# XC6SLX09-2FTG256C.net
KiCad netlist of a schematic drawn in Altium Designer
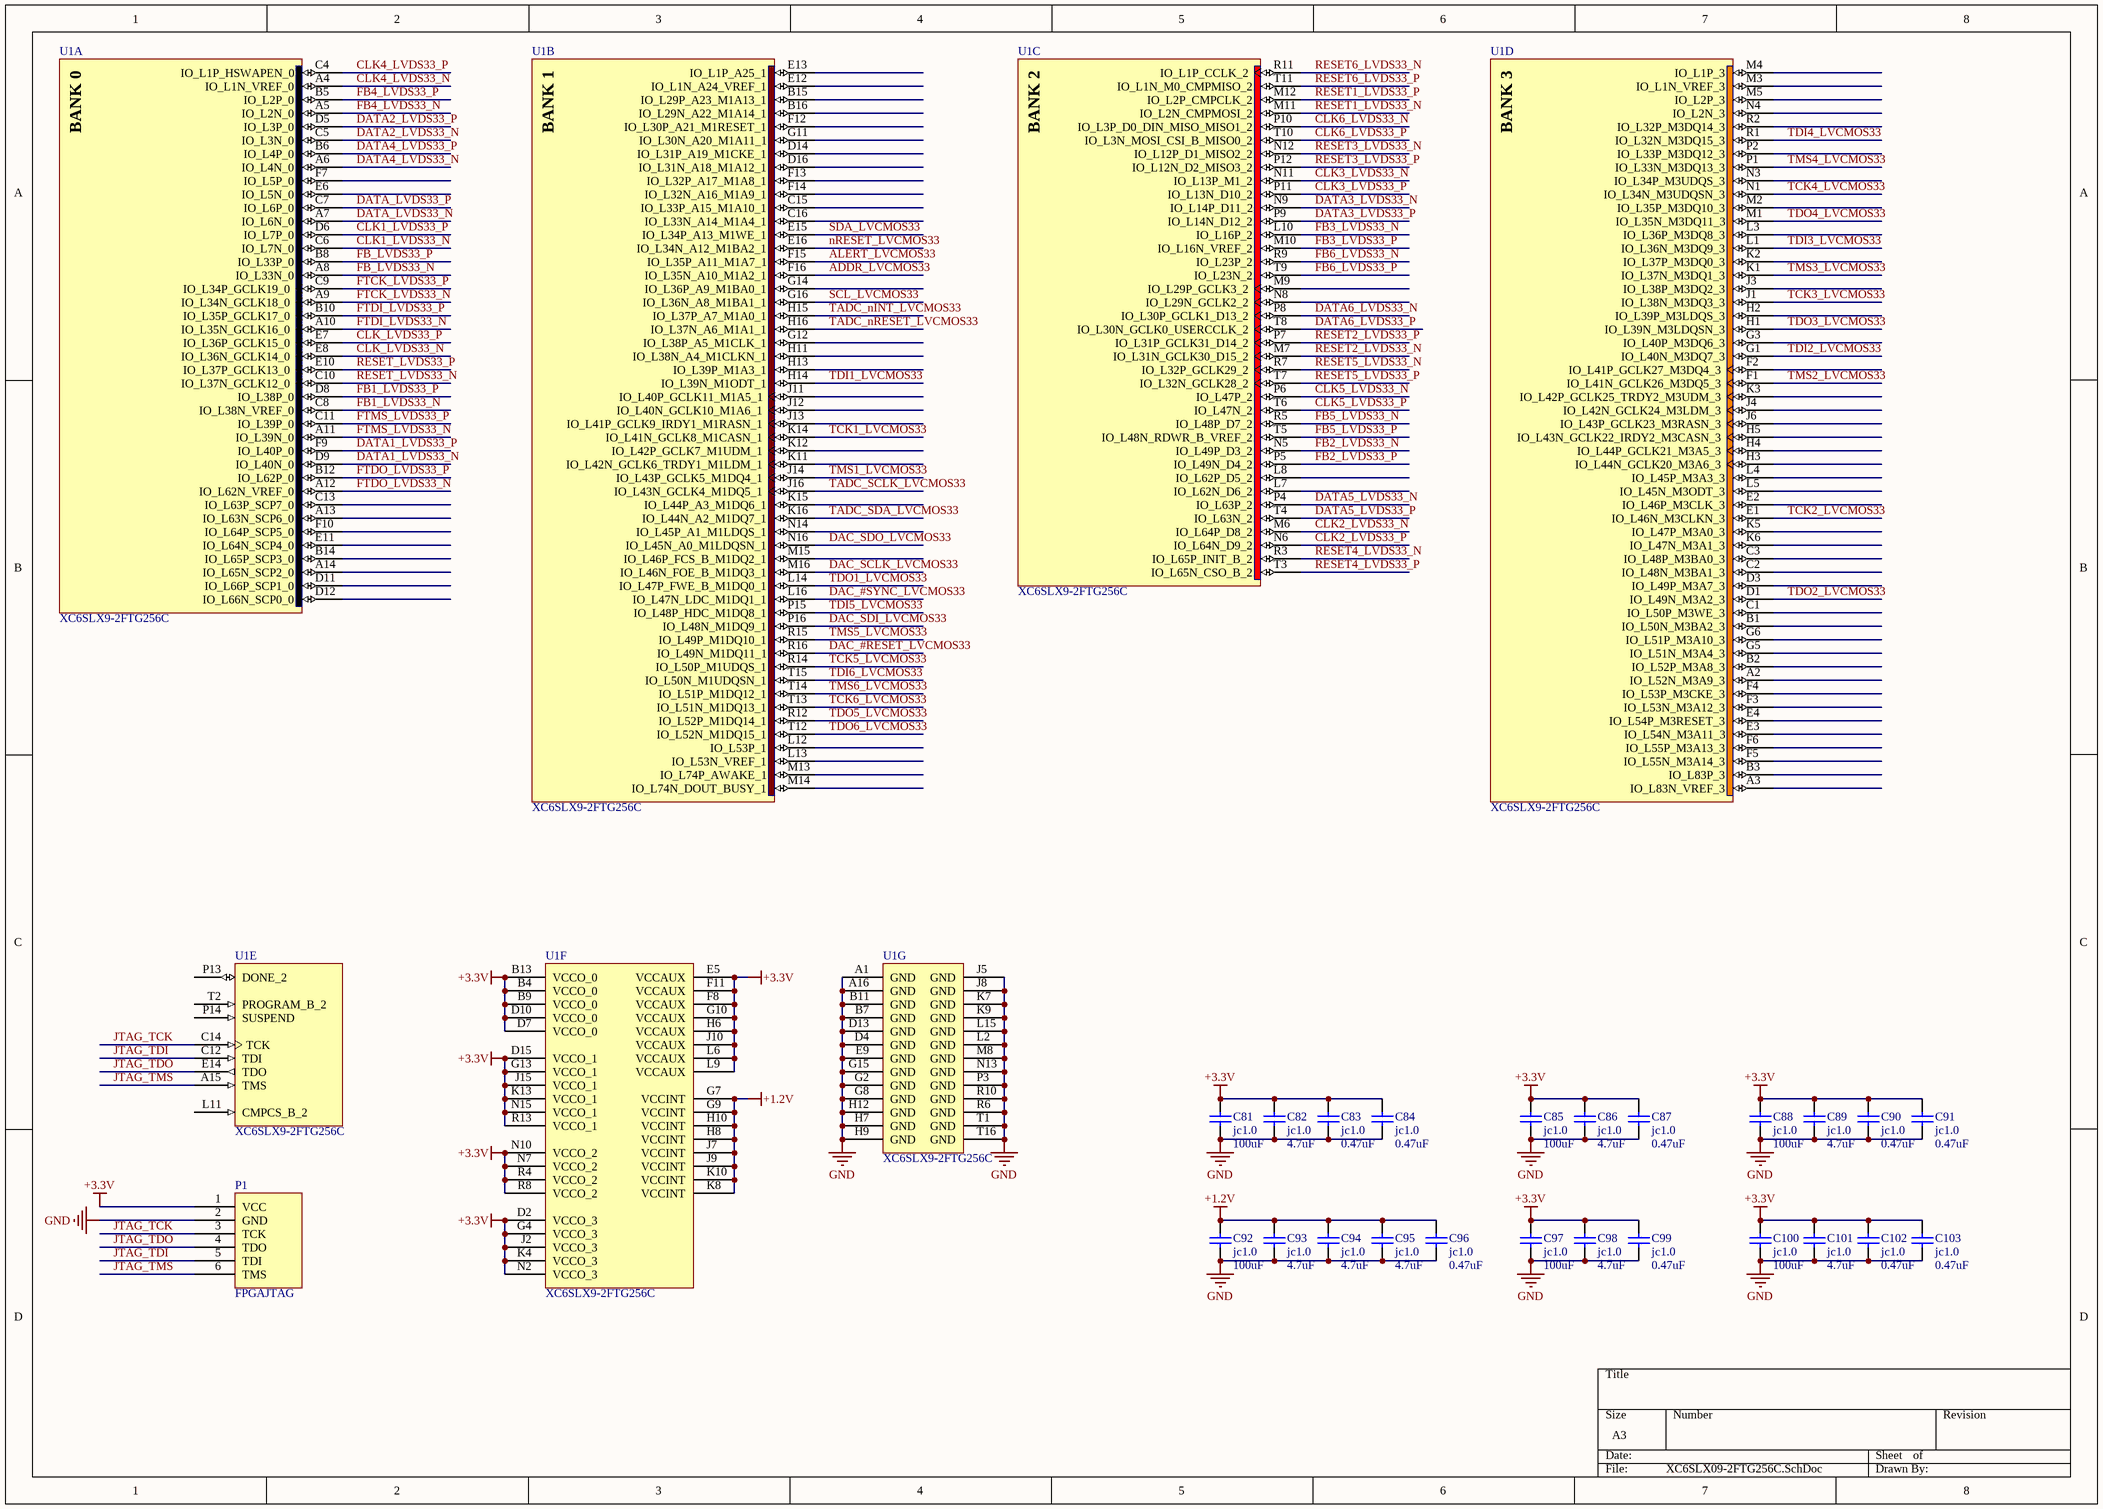
[diagram p0: XC6SLX09-2FTG256C.SchDoc]

(export (version "E")
  (design (tool "Eeschema 10.0.6"))
  (components
    (comp (ref "C81")
      (value "jc1.0")
      (footprint "0805")
      (description "Capacitor")
      (fields (field (name "ALTIUM_VALUE") "100uF") (field (name "PUBLISHER") "Altium Limited"))
      (libsource (lib "LIB01DXP2006SchLib") (part "Cap"))
    )
    (comp (ref "C82")
      (value "jc1.0")
      (footprint "0402")
      (description "Capacitor")
      (fields (field (name "ALTIUM_VALUE") "4.7uF") (field (name "PUBLISHER") "Altium Limited"))
      (libsource (lib "LIB01DXP2006SchLib") (part "Cap"))
    )
    (comp (ref "C83")
      (value "jc1.0")
      (footprint "0402")
      (description "Capacitor")
      (fields (field (name "ALTIUM_VALUE") "0.47uF") (field (name "PUBLISHER") "Altium Limited"))
      (libsource (lib "LIB01DXP2006SchLib") (part "Cap"))
    )
    (comp (ref "C84")
      (value "jc1.0")
      (footprint "0402")
      (description "Capacitor")
      (fields (field (name "ALTIUM_VALUE") "0.47uF") (field (name "PUBLISHER") "Altium Limited"))
      (libsource (lib "LIB01DXP2006SchLib") (part "Cap"))
    )
    (comp (ref "C85")
      (value "jc1.0")
      (footprint "0805")
      (description "Capacitor")
      (fields (field (name "ALTIUM_VALUE") "100uF") (field (name "PUBLISHER") "Altium Limited"))
      (libsource (lib "LIB01DXP2006SchLib") (part "Cap"))
    )
    (comp (ref "C86")
      (value "jc1.0")
      (footprint "0402")
      (description "Capacitor")
      (fields (field (name "ALTIUM_VALUE") "4.7uF") (field (name "PUBLISHER") "Altium Limited"))
      (libsource (lib "LIB01DXP2006SchLib") (part "Cap"))
    )
    (comp (ref "C87")
      (value "jc1.0")
      (footprint "0402")
      (description "Capacitor")
      (fields (field (name "ALTIUM_VALUE") "0.47uF") (field (name "PUBLISHER") "Altium Limited"))
      (libsource (lib "LIB01DXP2006SchLib") (part "Cap"))
    )
    (comp (ref "C88")
      (value "jc1.0")
      (footprint "0805")
      (description "Capacitor")
      (fields (field (name "ALTIUM_VALUE") "100uF") (field (name "PUBLISHER") "Altium Limited"))
      (libsource (lib "LIB01DXP2006SchLib") (part "Cap"))
    )
    (comp (ref "C89")
      (value "jc1.0")
      (footprint "0402")
      (description "Capacitor")
      (fields (field (name "ALTIUM_VALUE") "4.7uF") (field (name "PUBLISHER") "Altium Limited"))
      (libsource (lib "LIB01DXP2006SchLib") (part "Cap"))
    )
    (comp (ref "C90")
      (value "jc1.0")
      (footprint "0402")
      (description "Capacitor")
      (fields (field (name "ALTIUM_VALUE") "0.47uF") (field (name "PUBLISHER") "Altium Limited"))
      (libsource (lib "LIB01DXP2006SchLib") (part "Cap"))
    )
    (comp (ref "C91")
      (value "jc1.0")
      (footprint "0402")
      (description "Capacitor")
      (fields (field (name "ALTIUM_VALUE") "0.47uF") (field (name "PUBLISHER") "Altium Limited"))
      (libsource (lib "LIB01DXP2006SchLib") (part "Cap"))
    )
    (comp (ref "C92")
      (value "jc1.0")
      (footprint "0805")
      (description "Capacitor")
      (fields (field (name "ALTIUM_VALUE") "100uF") (field (name "PUBLISHER") "Altium Limited"))
      (libsource (lib "LIB01DXP2006SchLib") (part "Cap"))
    )
    (comp (ref "C93")
      (value "jc1.0")
      (footprint "0402")
      (description "Capacitor")
      (fields (field (name "ALTIUM_VALUE") "4.7uF") (field (name "PUBLISHER") "Altium Limited"))
      (libsource (lib "LIB01DXP2006SchLib") (part "Cap"))
    )
    (comp (ref "C94")
      (value "jc1.0")
      (footprint "0402")
      (description "Capacitor")
      (fields (field (name "ALTIUM_VALUE") "4.7uF") (field (name "PUBLISHER") "Altium Limited"))
      (libsource (lib "LIB01DXP2006SchLib") (part "Cap"))
    )
    (comp (ref "C95")
      (value "jc1.0")
      (footprint "0402")
      (description "Capacitor")
      (fields (field (name "ALTIUM_VALUE") "4.7uF") (field (name "PUBLISHER") "Altium Limited"))
      (libsource (lib "LIB01DXP2006SchLib") (part "Cap"))
    )
    (comp (ref "C96")
      (value "jc1.0")
      (footprint "0402")
      (description "Capacitor")
      (fields (field (name "ALTIUM_VALUE") "0.47uF") (field (name "PUBLISHER") "Altium Limited"))
      (libsource (lib "LIB01DXP2006SchLib") (part "Cap"))
    )
    (comp (ref "C97")
      (value "jc1.0")
      (footprint "0805")
      (description "Capacitor")
      (fields (field (name "ALTIUM_VALUE") "100uF") (field (name "PUBLISHER") "Altium Limited"))
      (libsource (lib "LIB01DXP2006SchLib") (part "Cap"))
    )
    (comp (ref "C98")
      (value "jc1.0")
      (footprint "0402")
      (description "Capacitor")
      (fields (field (name "ALTIUM_VALUE") "4.7uF") (field (name "PUBLISHER") "Altium Limited"))
      (libsource (lib "LIB01DXP2006SchLib") (part "Cap"))
    )
    (comp (ref "C99")
      (value "jc1.0")
      (footprint "0402")
      (description "Capacitor")
      (fields (field (name "ALTIUM_VALUE") "0.47uF") (field (name "PUBLISHER") "Altium Limited"))
      (libsource (lib "LIB01DXP2006SchLib") (part "Cap"))
    )
    (comp (ref "C100")
      (value "jc1.0")
      (footprint "0805")
      (description "Capacitor")
      (fields (field (name "ALTIUM_VALUE") "100uF") (field (name "PUBLISHER") "Altium Limited"))
      (libsource (lib "LIB01DXP2006SchLib") (part "Cap"))
    )
    (comp (ref "C101")
      (value "jc1.0")
      (footprint "0402")
      (description "Capacitor")
      (fields (field (name "ALTIUM_VALUE") "4.7uF") (field (name "PUBLISHER") "Altium Limited"))
      (libsource (lib "LIB01DXP2006SchLib") (part "Cap"))
    )
    (comp (ref "C102")
      (value "jc1.0")
      (footprint "0402")
      (description "Capacitor")
      (fields (field (name "ALTIUM_VALUE") "0.47uF") (field (name "PUBLISHER") "Altium Limited"))
      (libsource (lib "LIB01DXP2006SchLib") (part "Cap"))
    )
    (comp (ref "C103")
      (value "jc1.0")
      (footprint "0402")
      (description "Capacitor")
      (fields (field (name "ALTIUM_VALUE") "0.47uF") (field (name "PUBLISHER") "Altium Limited"))
      (libsource (lib "LIB01DXP2006SchLib") (part "Cap"))
    )
    (comp (ref "P1")
      (value "FPGAJTAG")
      (footprint "SIP6")
      (libsource (lib "LIB01DXP2006SchLib") (part "FPGAJTAGHEADER"))
    )
    (comp (ref "U1")
      (value "XC6SLX9-2FTG256C")
      (footprint "FTG256")
      (libsource (lib "Spartan-6") (part "XC6SLX9-2FTG256C"))
    )
  )
  (nets
    (net (code "1") (name "+1.2V") (class "Default")
      (node (ref "C92") (pin "2") (pinfunction "2_2") (pintype "passive"))
      (node (ref "C93") (pin "2") (pinfunction "2_2") (pintype "passive"))
      (node (ref "C94") (pin "2") (pinfunction "2_2") (pintype "passive"))
      (node (ref "C95") (pin "2") (pinfunction "2_2") (pintype "passive"))
      (node (ref "C96") (pin "2") (pinfunction "2_2") (pintype "passive"))
      (node (ref "U1") (pin "G7") (pinfunction "VCCINT_G7") (pintype "power_in"))
      (node (ref "U1") (pin "G9") (pinfunction "VCCINT_G9") (pintype "power_in"))
      (node (ref "U1") (pin "H10") (pinfunction "VCCINT_H10") (pintype "power_in"))
      (node (ref "U1") (pin "H8") (pinfunction "VCCINT_H8") (pintype "power_in"))
      (node (ref "U1") (pin "J7") (pinfunction "VCCINT_J7") (pintype "power_in"))
      (node (ref "U1") (pin "J9") (pinfunction "VCCINT_J9") (pintype "power_in"))
      (node (ref "U1") (pin "K10") (pinfunction "VCCINT_K10") (pintype "power_in"))
      (node (ref "U1") (pin "K8") (pinfunction "VCCINT_K8") (pintype "power_in"))
    )
    (net (code "2") (name "+3.3V") (class "Default")
      (node (ref "C100") (pin "2") (pinfunction "2_2") (pintype "passive"))
      (node (ref "C101") (pin "2") (pinfunction "2_2") (pintype "passive"))
      (node (ref "C102") (pin "2") (pinfunction "2_2") (pintype "passive"))
      (node (ref "C103") (pin "2") (pinfunction "2_2") (pintype "passive"))
      (node (ref "C81") (pin "2") (pinfunction "2_2") (pintype "passive"))
      (node (ref "C82") (pin "2") (pinfunction "2_2") (pintype "passive"))
      (node (ref "C83") (pin "2") (pinfunction "2_2") (pintype "passive"))
      (node (ref "C84") (pin "2") (pinfunction "2_2") (pintype "passive"))
      (node (ref "C85") (pin "2") (pinfunction "2_2") (pintype "passive"))
      (node (ref "C86") (pin "2") (pinfunction "2_2") (pintype "passive"))
      (node (ref "C87") (pin "2") (pinfunction "2_2") (pintype "passive"))
      (node (ref "C88") (pin "2") (pinfunction "2_2") (pintype "passive"))
      (node (ref "C89") (pin "2") (pinfunction "2_2") (pintype "passive"))
      (node (ref "C90") (pin "2") (pinfunction "2_2") (pintype "passive"))
      (node (ref "C91") (pin "2") (pinfunction "2_2") (pintype "passive"))
      (node (ref "C97") (pin "2") (pinfunction "2_2") (pintype "passive"))
      (node (ref "C98") (pin "2") (pinfunction "2_2") (pintype "passive"))
      (node (ref "C99") (pin "2") (pinfunction "2_2") (pintype "passive"))
      (node (ref "P1") (pin "1") (pinfunction "VCC_1") (pintype "passive"))
      (node (ref "U1") (pin "B13") (pinfunction "VCCO_0_B13") (pintype "power_in"))
      (node (ref "U1") (pin "B4") (pinfunction "VCCO_0_B4") (pintype "power_in"))
      (node (ref "U1") (pin "B9") (pinfunction "VCCO_0_B9") (pintype "power_in"))
      (node (ref "U1") (pin "D10") (pinfunction "VCCO_0_D10") (pintype "power_in"))
      (node (ref "U1") (pin "D15") (pinfunction "VCCO_1_D15") (pintype "power_in"))
      (node (ref "U1") (pin "D2") (pinfunction "VCCO_3_D2") (pintype "power_in"))
      (node (ref "U1") (pin "D7") (pinfunction "VCCO_0_D7") (pintype "power_in"))
      (node (ref "U1") (pin "E5") (pinfunction "VCCAUX_E5") (pintype "power_in"))
      (node (ref "U1") (pin "F11") (pinfunction "VCCAUX_F11") (pintype "power_in"))
      (node (ref "U1") (pin "F8") (pinfunction "VCCAUX_F8") (pintype "power_in"))
      (node (ref "U1") (pin "G10") (pinfunction "VCCAUX_G10") (pintype "power_in"))
      (node (ref "U1") (pin "G13") (pinfunction "VCCO_1_G13") (pintype "power_in"))
      (node (ref "U1") (pin "G4") (pinfunction "VCCO_3_G4") (pintype "power_in"))
      (node (ref "U1") (pin "H6") (pinfunction "VCCAUX_H6") (pintype "power_in"))
      (node (ref "U1") (pin "J10") (pinfunction "VCCAUX_J10") (pintype "power_in"))
      (node (ref "U1") (pin "J15") (pinfunction "VCCO_1_J15") (pintype "power_in"))
      (node (ref "U1") (pin "J2") (pinfunction "VCCO_3_J2") (pintype "power_in"))
      (node (ref "U1") (pin "K13") (pinfunction "VCCO_1_K13") (pintype "power_in"))
      (node (ref "U1") (pin "K4") (pinfunction "VCCO_3_K4") (pintype "power_in"))
      (node (ref "U1") (pin "L6") (pinfunction "VCCAUX_L6") (pintype "power_in"))
      (node (ref "U1") (pin "L9") (pinfunction "VCCAUX_L9") (pintype "power_in"))
      (node (ref "U1") (pin "N10") (pinfunction "VCCO_2_N10") (pintype "power_in"))
      (node (ref "U1") (pin "N15") (pinfunction "VCCO_1_N15") (pintype "power_in"))
      (node (ref "U1") (pin "N2") (pinfunction "VCCO_3_N2") (pintype "power_in"))
      (node (ref "U1") (pin "N7") (pinfunction "VCCO_2_N7") (pintype "power_in"))
      (node (ref "U1") (pin "R13") (pinfunction "VCCO_1_R13") (pintype "power_in"))
      (node (ref "U1") (pin "R4") (pinfunction "VCCO_2_R4") (pintype "power_in"))
      (node (ref "U1") (pin "R8") (pinfunction "VCCO_2_R8") (pintype "power_in"))
    )
    (net (code "3") (name "/ADDR_LVCMOS33") (class "Default")
      (node (ref "U1") (pin "F16") (pinfunction "IO_L35N_A10_M1A2_1_F16") (pintype "bidirectional"))
    )
    (net (code "4") (name "/ALERT_LVCMOS33") (class "Default")
      (node (ref "U1") (pin "F15") (pinfunction "IO_L35P_A11_M1A7_1_F15") (pintype "bidirectional"))
    )
    (net (code "5") (name "/CLK1_LVDS33_N") (class "Default")
      (node (ref "U1") (pin "C6") (pinfunction "IO_L7N_0_C6") (pintype "bidirectional"))
    )
    (net (code "6") (name "/CLK1_LVDS33_P") (class "Default")
      (node (ref "U1") (pin "D6") (pinfunction "IO_L7P_0_D6") (pintype "bidirectional"))
    )
    (net (code "7") (name "/CLK2_LVDS33_N") (class "Default")
      (node (ref "U1") (pin "M6") (pinfunction "IO_L64P_D8_2_M6") (pintype "bidirectional"))
    )
    (net (code "8") (name "/CLK2_LVDS33_P") (class "Default")
      (node (ref "U1") (pin "N6") (pinfunction "IO_L64N_D9_2_N6") (pintype "bidirectional"))
    )
    (net (code "9") (name "/CLK3_LVDS33_N") (class "Default")
      (node (ref "U1") (pin "N11") (pinfunction "IO_L13P_M1_2_N11") (pintype "bidirectional"))
    )
    (net (code "10") (name "/CLK3_LVDS33_P") (class "Default")
      (node (ref "U1") (pin "P11") (pinfunction "IO_L13N_D10_2_P11") (pintype "bidirectional"))
    )
    (net (code "11") (name "/CLK4_LVDS33_N") (class "Default")
      (node (ref "U1") (pin "A4") (pinfunction "IO_L1N_VREF_0_A4") (pintype "bidirectional"))
    )
    (net (code "12") (name "/CLK4_LVDS33_P") (class "Default")
      (node (ref "U1") (pin "C4") (pinfunction "IO_L1P_HSWAPEN_0_C4") (pintype "bidirectional"))
    )
    (net (code "13") (name "/CLK5_LVDS33_N") (class "Default")
      (node (ref "U1") (pin "P6") (pinfunction "IO_L47P_2_P6") (pintype "bidirectional"))
    )
    (net (code "14") (name "/CLK5_LVDS33_P") (class "Default")
      (node (ref "U1") (pin "T6") (pinfunction "IO_L47N_2_T6") (pintype "bidirectional"))
    )
    (net (code "15") (name "/CLK6_LVDS33_N") (class "Default")
      (node (ref "U1") (pin "P10") (pinfunction "IO_L3P_D0_DIN_MISO_MISO1_2_P10") (pintype "bidirectional"))
    )
    (net (code "16") (name "/CLK6_LVDS33_P") (class "Default")
      (node (ref "U1") (pin "T10") (pinfunction "IO_L3N_MOSI_CSI_B_MISO0_2_T10") (pintype "bidirectional"))
    )
    (net (code "17") (name "/CLK_LVDS33_N") (class "Default")
      (node (ref "U1") (pin "E8") (pinfunction "IO_L36N_GCLK14_0_E8") (pintype "bidirectional"))
    )
    (net (code "18") (name "/CLK_LVDS33_P") (class "Default")
      (node (ref "U1") (pin "E7") (pinfunction "IO_L36P_GCLK15_0_E7") (pintype "bidirectional"))
    )
    (net (code "19") (name "/DAC_#RESET_LVCMOS33") (class "Default")
      (node (ref "U1") (pin "R16") (pinfunction "IO_L49N_M1DQ11_1_R16") (pintype "bidirectional"))
    )
    (net (code "20") (name "/DAC_#SYNC_LVCMOS33") (class "Default")
      (node (ref "U1") (pin "L16") (pinfunction "IO_L47N_LDC_M1DQ1_1_L16") (pintype "bidirectional"))
    )
    (net (code "21") (name "/DAC_SCLK_LVCMOS33") (class "Default")
      (node (ref "U1") (pin "M16") (pinfunction "IO_L46N_FOE_B_M1DQ3_1_M16") (pintype "bidirectional"))
    )
    (net (code "22") (name "/DAC_SDI_LVCMOS33") (class "Default")
      (node (ref "U1") (pin "P16") (pinfunction "IO_L48N_M1DQ9_1_P16") (pintype "bidirectional"))
    )
    (net (code "23") (name "/DAC_SDO_LVCMOS33") (class "Default")
      (node (ref "U1") (pin "N16") (pinfunction "IO_L45N_A0_M1LDQSN_1_N16") (pintype "bidirectional"))
    )
    (net (code "24") (name "/DATA1_LVDS33_N") (class "Default")
      (node (ref "U1") (pin "D9") (pinfunction "IO_L40N_0_D9") (pintype "bidirectional"))
    )
    (net (code "25") (name "/DATA1_LVDS33_P") (class "Default")
      (node (ref "U1") (pin "F9") (pinfunction "IO_L40P_0_F9") (pintype "bidirectional"))
    )
    (net (code "26") (name "/DATA2_LVDS33_N") (class "Default")
      (node (ref "U1") (pin "C5") (pinfunction "IO_L3N_0_C5") (pintype "bidirectional"))
    )
    (net (code "27") (name "/DATA2_LVDS33_P") (class "Default")
      (node (ref "U1") (pin "D5") (pinfunction "IO_L3P_0_D5") (pintype "bidirectional"))
    )
    (net (code "28") (name "/DATA3_LVDS33_N") (class "Default")
      (node (ref "U1") (pin "N9") (pinfunction "IO_L14P_D11_2_N9") (pintype "bidirectional"))
    )
    (net (code "29") (name "/DATA3_LVDS33_P") (class "Default")
      (node (ref "U1") (pin "P9") (pinfunction "IO_L14N_D12_2_P9") (pintype "bidirectional"))
    )
    (net (code "30") (name "/DATA4_LVDS33_N") (class "Default")
      (node (ref "U1") (pin "A6") (pinfunction "IO_L4N_0_A6") (pintype "bidirectional"))
    )
    (net (code "31") (name "/DATA4_LVDS33_P") (class "Default")
      (node (ref "U1") (pin "B6") (pinfunction "IO_L4P_0_B6") (pintype "bidirectional"))
    )
    (net (code "32") (name "/DATA5_LVDS33_N") (class "Default")
      (node (ref "U1") (pin "P4") (pinfunction "IO_L63P_2_P4") (pintype "bidirectional"))
    )
    (net (code "33") (name "/DATA5_LVDS33_P") (class "Default")
      (node (ref "U1") (pin "T4") (pinfunction "IO_L63N_2_T4") (pintype "bidirectional"))
    )
    (net (code "34") (name "/DATA6_LVDS33_N") (class "Default")
      (node (ref "U1") (pin "P8") (pinfunction "IO_L30P_GCLK1_D13_2_P8") (pintype "bidirectional"))
    )
    (net (code "35") (name "/DATA6_LVDS33_P") (class "Default")
      (node (ref "U1") (pin "T8") (pinfunction "IO_L30N_GCLK0_USERCCLK_2_T8") (pintype "bidirectional"))
    )
    (net (code "36") (name "/DATA_LVDS33_N") (class "Default")
      (node (ref "U1") (pin "A7") (pinfunction "IO_L6N_0_A7") (pintype "bidirectional"))
    )
    (net (code "37") (name "/DATA_LVDS33_P") (class "Default")
      (node (ref "U1") (pin "C7") (pinfunction "IO_L6P_0_C7") (pintype "bidirectional"))
    )
    (net (code "38") (name "/FB1_LVDS33_N") (class "Default")
      (node (ref "U1") (pin "C8") (pinfunction "IO_L38N_VREF_0_C8") (pintype "bidirectional"))
    )
    (net (code "39") (name "/FB1_LVDS33_P") (class "Default")
      (node (ref "U1") (pin "D8") (pinfunction "IO_L38P_0_D8") (pintype "bidirectional"))
    )
    (net (code "40") (name "/FB2_LVDS33_N") (class "Default")
      (node (ref "U1") (pin "N5") (pinfunction "IO_L49P_D3_2_N5") (pintype "bidirectional"))
    )
    (net (code "41") (name "/FB2_LVDS33_P") (class "Default")
      (node (ref "U1") (pin "P5") (pinfunction "IO_L49N_D4_2_P5") (pintype "bidirectional"))
    )
    (net (code "42") (name "/FB3_LVDS33_N") (class "Default")
      (node (ref "U1") (pin "L10") (pinfunction "IO_L16P_2_L10") (pintype "bidirectional"))
    )
    (net (code "43") (name "/FB3_LVDS33_P") (class "Default")
      (node (ref "U1") (pin "M10") (pinfunction "IO_L16N_VREF_2_M10") (pintype "bidirectional"))
    )
    (net (code "44") (name "/FB4_LVDS33_N") (class "Default")
      (node (ref "U1") (pin "A5") (pinfunction "IO_L2N_0_A5") (pintype "bidirectional"))
    )
    (net (code "45") (name "/FB4_LVDS33_P") (class "Default")
      (node (ref "U1") (pin "B5") (pinfunction "IO_L2P_0_B5") (pintype "bidirectional"))
    )
    (net (code "46") (name "/FB5_LVDS33_N") (class "Default")
      (node (ref "U1") (pin "R5") (pinfunction "IO_L48P_D7_2_R5") (pintype "bidirectional"))
    )
    (net (code "47") (name "/FB5_LVDS33_P") (class "Default")
      (node (ref "U1") (pin "T5") (pinfunction "IO_L48N_RDWR_B_VREF_2_T5") (pintype "bidirectional"))
    )
    (net (code "48") (name "/FB6_LVDS33_N") (class "Default")
      (node (ref "U1") (pin "R9") (pinfunction "IO_L23P_2_R9") (pintype "bidirectional"))
    )
    (net (code "49") (name "/FB6_LVDS33_P") (class "Default")
      (node (ref "U1") (pin "T9") (pinfunction "IO_L23N_2_T9") (pintype "bidirectional"))
    )
    (net (code "50") (name "/FB_LVDS33_N") (class "Default")
      (node (ref "U1") (pin "A8") (pinfunction "IO_L33N_0_A8") (pintype "bidirectional"))
    )
    (net (code "51") (name "/FB_LVDS33_P") (class "Default")
      (node (ref "U1") (pin "B8") (pinfunction "IO_L33P_0_B8") (pintype "bidirectional"))
    )
    (net (code "52") (name "/FTCK_LVDS33_N") (class "Default")
      (node (ref "U1") (pin "A9") (pinfunction "IO_L34N_GCLK18_0_A9") (pintype "bidirectional"))
    )
    (net (code "53") (name "/FTCK_LVDS33_P") (class "Default")
      (node (ref "U1") (pin "C9") (pinfunction "IO_L34P_GCLK19_0_C9") (pintype "bidirectional"))
    )
    (net (code "54") (name "/FTDI_LVDS33_N") (class "Default")
      (node (ref "U1") (pin "A10") (pinfunction "IO_L35N_GCLK16_0_A10") (pintype "bidirectional"))
    )
    (net (code "55") (name "/FTDI_LVDS33_P") (class "Default")
      (node (ref "U1") (pin "B10") (pinfunction "IO_L35P_GCLK17_0_B10") (pintype "bidirectional"))
    )
    (net (code "56") (name "/FTDO_LVDS33_N") (class "Default")
      (node (ref "U1") (pin "A12") (pinfunction "IO_L62N_VREF_0_A12") (pintype "bidirectional"))
    )
    (net (code "57") (name "/FTDO_LVDS33_P") (class "Default")
      (node (ref "U1") (pin "B12") (pinfunction "IO_L62P_0_B12") (pintype "bidirectional"))
    )
    (net (code "58") (name "/FTMS_LVDS33_N") (class "Default")
      (node (ref "U1") (pin "A11") (pinfunction "IO_L39N_0_A11") (pintype "bidirectional"))
    )
    (net (code "59") (name "/FTMS_LVDS33_P") (class "Default")
      (node (ref "U1") (pin "C11") (pinfunction "IO_L39P_0_C11") (pintype "bidirectional"))
    )
    (net (code "60") (name "/JTAG_TCK") (class "Default")
      (node (ref "P1") (pin "3") (pinfunction "TCK_3") (pintype "passive"))
      (node (ref "U1") (pin "C14") (pinfunction "TCK_C14") (pintype "input"))
    )
    (net (code "61") (name "/JTAG_TDI") (class "Default")
      (node (ref "P1") (pin "5") (pinfunction "TDI_5") (pintype "passive"))
      (node (ref "U1") (pin "C12") (pinfunction "TDI_C12") (pintype "input"))
    )
    (net (code "62") (name "/JTAG_TDO") (class "Default")
      (node (ref "P1") (pin "4") (pinfunction "TDO_4") (pintype "passive"))
      (node (ref "U1") (pin "E14") (pinfunction "TDO_E14") (pintype "output"))
    )
    (net (code "63") (name "/JTAG_TMS") (class "Default")
      (node (ref "P1") (pin "6") (pinfunction "TMS_6") (pintype "passive"))
      (node (ref "U1") (pin "A15") (pinfunction "TMS_A15") (pintype "input"))
    )
    (net (code "64") (name "/RESET1_LVDS33_N") (class "Default")
      (node (ref "U1") (pin "M11") (pinfunction "IO_L2N_CMPMOSI_2_M11") (pintype "bidirectional"))
    )
    (net (code "65") (name "/RESET1_LVDS33_P") (class "Default")
      (node (ref "U1") (pin "M12") (pinfunction "IO_L2P_CMPCLK_2_M12") (pintype "bidirectional"))
    )
    (net (code "66") (name "/RESET2_LVDS33_N") (class "Default")
      (node (ref "U1") (pin "M7") (pinfunction "IO_L31N_GCLK30_D15_2_M7") (pintype "bidirectional"))
    )
    (net (code "67") (name "/RESET2_LVDS33_P") (class "Default")
      (node (ref "U1") (pin "P7") (pinfunction "IO_L31P_GCLK31_D14_2_P7") (pintype "bidirectional"))
    )
    (net (code "68") (name "/RESET3_LVDS33_N") (class "Default")
      (node (ref "U1") (pin "N12") (pinfunction "IO_L12P_D1_MISO2_2_N12") (pintype "bidirectional"))
    )
    (net (code "69") (name "/RESET3_LVDS33_P") (class "Default")
      (node (ref "U1") (pin "P12") (pinfunction "IO_L12N_D2_MISO3_2_P12") (pintype "bidirectional"))
    )
    (net (code "70") (name "/RESET4_LVDS33_N") (class "Default")
      (node (ref "U1") (pin "R3") (pinfunction "IO_L65P_INIT_B_2_R3") (pintype "bidirectional"))
    )
    (net (code "71") (name "/RESET4_LVDS33_P") (class "Default")
      (node (ref "U1") (pin "T3") (pinfunction "IO_L65N_CSO_B_2_T3") (pintype "bidirectional"))
    )
    (net (code "72") (name "/RESET5_LVDS33_N") (class "Default")
      (node (ref "U1") (pin "R7") (pinfunction "IO_L32P_GCLK29_2_R7") (pintype "bidirectional"))
    )
    (net (code "73") (name "/RESET5_LVDS33_P") (class "Default")
      (node (ref "U1") (pin "T7") (pinfunction "IO_L32N_GCLK28_2_T7") (pintype "bidirectional"))
    )
    (net (code "74") (name "/RESET6_LVDS33_N") (class "Default")
      (node (ref "U1") (pin "R11") (pinfunction "IO_L1P_CCLK_2_R11") (pintype "bidirectional"))
    )
    (net (code "75") (name "/RESET6_LVDS33_P") (class "Default")
      (node (ref "U1") (pin "T11") (pinfunction "IO_L1N_M0_CMPMISO_2_T11") (pintype "bidirectional"))
    )
    (net (code "76") (name "/RESET_LVDS33_N") (class "Default")
      (node (ref "U1") (pin "C10") (pinfunction "IO_L37N_GCLK12_0_C10") (pintype "bidirectional"))
    )
    (net (code "77") (name "/RESET_LVDS33_P") (class "Default")
      (node (ref "U1") (pin "E10") (pinfunction "IO_L37P_GCLK13_0_E10") (pintype "bidirectional"))
    )
    (net (code "78") (name "/SCL_LVCMOS33") (class "Default")
      (node (ref "U1") (pin "G16") (pinfunction "IO_L36N_A8_M1BA1_1_G16") (pintype "bidirectional"))
    )
    (net (code "79") (name "/SDA_LVCMOS33") (class "Default")
      (node (ref "U1") (pin "E15") (pinfunction "IO_L34P_A13_M1WE_1_E15") (pintype "bidirectional"))
    )
    (net (code "80") (name "/TADC_SCLK_LVCMOS33") (class "Default")
      (node (ref "U1") (pin "J16") (pinfunction "IO_L43N_GCLK4_M1DQ5_1_J16") (pintype "bidirectional"))
    )
    (net (code "81") (name "/TADC_SDA_LVCMOS33") (class "Default")
      (node (ref "U1") (pin "K16") (pinfunction "IO_L44N_A2_M1DQ7_1_K16") (pintype "bidirectional"))
    )
    (net (code "82") (name "/TADC_nINT_LVCMOS33") (class "Default")
      (node (ref "U1") (pin "H15") (pinfunction "IO_L37P_A7_M1A0_1_H15") (pintype "bidirectional"))
    )
    (net (code "83") (name "/TADC_nRESET_LVCMOS33") (class "Default")
      (node (ref "U1") (pin "H16") (pinfunction "IO_L37N_A6_M1A1_1_H16") (pintype "bidirectional"))
    )
    (net (code "84") (name "/TCK1_LVCMOS33") (class "Default")
      (node (ref "U1") (pin "K14") (pinfunction "IO_L41N_GCLK8_M1CASN_1_K14") (pintype "bidirectional"))
    )
    (net (code "85") (name "/TCK2_LVCMOS33") (class "Default")
      (node (ref "U1") (pin "E1") (pinfunction "IO_L46N_M3CLKN_3_E1") (pintype "bidirectional"))
    )
    (net (code "86") (name "/TCK3_LVCMOS33") (class "Default")
      (node (ref "U1") (pin "J1") (pinfunction "IO_L38N_M3DQ3_3_J1") (pintype "bidirectional"))
    )
    (net (code "87") (name "/TCK4_LVCMOS33") (class "Default")
      (node (ref "U1") (pin "N1") (pinfunction "IO_L34N_M3UDQSN_3_N1") (pintype "bidirectional"))
    )
    (net (code "88") (name "/TCK5_LVCMOS33") (class "Default")
      (node (ref "U1") (pin "R14") (pinfunction "IO_L50P_M1UDQS_1_R14") (pintype "bidirectional"))
    )
    (net (code "89") (name "/TCK6_LVCMOS33") (class "Default")
      (node (ref "U1") (pin "T13") (pinfunction "IO_L51N_M1DQ13_1_T13") (pintype "bidirectional"))
    )
    (net (code "90") (name "/TDI1_LVCMOS33") (class "Default")
      (node (ref "U1") (pin "H14") (pinfunction "IO_L39N_M1ODT_1_H14") (pintype "bidirectional"))
    )
    (net (code "91") (name "/TDI2_LVCMOS33") (class "Default")
      (node (ref "U1") (pin "G1") (pinfunction "IO_L40N_M3DQ7_3_G1") (pintype "bidirectional"))
    )
    (net (code "92") (name "/TDI3_LVCMOS33") (class "Default")
      (node (ref "U1") (pin "L1") (pinfunction "IO_L36N_M3DQ9_3_L1") (pintype "bidirectional"))
    )
    (net (code "93") (name "/TDI4_LVCMOS33") (class "Default")
      (node (ref "U1") (pin "R1") (pinfunction "IO_L32N_M3DQ15_3_R1") (pintype "bidirectional"))
    )
    (net (code "94") (name "/TDI5_LVCMOS33") (class "Default")
      (node (ref "U1") (pin "P15") (pinfunction "IO_L48P_HDC_M1DQ8_1_P15") (pintype "bidirectional"))
    )
    (net (code "95") (name "/TDI6_LVCMOS33") (class "Default")
      (node (ref "U1") (pin "T15") (pinfunction "IO_L50N_M1UDQSN_1_T15") (pintype "bidirectional"))
    )
    (net (code "96") (name "/TDO1_LVCMOS33") (class "Default")
      (node (ref "U1") (pin "L14") (pinfunction "IO_L47P_FWE_B_M1DQ0_1_L14") (pintype "bidirectional"))
    )
    (net (code "97") (name "/TDO2_LVCMOS33") (class "Default")
      (node (ref "U1") (pin "D1") (pinfunction "IO_L49N_M3A2_3_D1") (pintype "bidirectional"))
    )
    (net (code "98") (name "/TDO3_LVCMOS33") (class "Default")
      (node (ref "U1") (pin "H1") (pinfunction "IO_L39N_M3LDQSN_3_H1") (pintype "bidirectional"))
    )
    (net (code "99") (name "/TDO4_LVCMOS33") (class "Default")
      (node (ref "U1") (pin "M1") (pinfunction "IO_L35N_M3DQ11_3_M1") (pintype "bidirectional"))
    )
    (net (code "100") (name "/TDO5_LVCMOS33") (class "Default")
      (node (ref "U1") (pin "R12") (pinfunction "IO_L52P_M1DQ14_1_R12") (pintype "bidirectional"))
    )
    (net (code "101") (name "/TDO6_LVCMOS33") (class "Default")
      (node (ref "U1") (pin "T12") (pinfunction "IO_L52N_M1DQ15_1_T12") (pintype "bidirectional"))
    )
    (net (code "102") (name "/TMS1_LVCMOS33") (class "Default")
      (node (ref "U1") (pin "J14") (pinfunction "IO_L43P_GCLK5_M1DQ4_1_J14") (pintype "bidirectional"))
    )
    (net (code "103") (name "/TMS2_LVCMOS33") (class "Default")
      (node (ref "U1") (pin "F1") (pinfunction "IO_L41N_GCLK26_M3DQ5_3_F1") (pintype "bidirectional"))
    )
    (net (code "104") (name "/TMS3_LVCMOS33") (class "Default")
      (node (ref "U1") (pin "K1") (pinfunction "IO_L37N_M3DQ1_3_K1") (pintype "bidirectional"))
    )
    (net (code "105") (name "/TMS4_LVCMOS33") (class "Default")
      (node (ref "U1") (pin "P1") (pinfunction "IO_L33N_M3DQ13_3_P1") (pintype "bidirectional"))
    )
    (net (code "106") (name "/TMS5_LVCMOS33") (class "Default")
      (node (ref "U1") (pin "R15") (pinfunction "IO_L49P_M1DQ10_1_R15") (pintype "bidirectional"))
    )
    (net (code "107") (name "/TMS6_LVCMOS33") (class "Default")
      (node (ref "U1") (pin "T14") (pinfunction "IO_L51P_M1DQ12_1_T14") (pintype "bidirectional"))
    )
    (net (code "108") (name "/nRESET_LVCMOS33") (class "Default")
      (node (ref "U1") (pin "E16") (pinfunction "IO_L34N_A12_M1BA2_1_E16") (pintype "bidirectional"))
    )
    (net (code "109") (name "GND") (class "Default")
      (node (ref "C100") (pin "1") (pinfunction "1_1") (pintype "passive"))
      (node (ref "C101") (pin "1") (pinfunction "1_1") (pintype "passive"))
      (node (ref "C102") (pin "1") (pinfunction "1_1") (pintype "passive"))
      (node (ref "C103") (pin "1") (pinfunction "1_1") (pintype "passive"))
      (node (ref "C81") (pin "1") (pinfunction "1_1") (pintype "passive"))
      (node (ref "C82") (pin "1") (pinfunction "1_1") (pintype "passive"))
      (node (ref "C83") (pin "1") (pinfunction "1_1") (pintype "passive"))
      (node (ref "C84") (pin "1") (pinfunction "1_1") (pintype "passive"))
      (node (ref "C85") (pin "1") (pinfunction "1_1") (pintype "passive"))
      (node (ref "C86") (pin "1") (pinfunction "1_1") (pintype "passive"))
      (node (ref "C87") (pin "1") (pinfunction "1_1") (pintype "passive"))
      (node (ref "C88") (pin "1") (pinfunction "1_1") (pintype "passive"))
      (node (ref "C89") (pin "1") (pinfunction "1_1") (pintype "passive"))
      (node (ref "C90") (pin "1") (pinfunction "1_1") (pintype "passive"))
      (node (ref "C91") (pin "1") (pinfunction "1_1") (pintype "passive"))
      (node (ref "C92") (pin "1") (pinfunction "1_1") (pintype "passive"))
      (node (ref "C93") (pin "1") (pinfunction "1_1") (pintype "passive"))
      (node (ref "C94") (pin "1") (pinfunction "1_1") (pintype "passive"))
      (node (ref "C95") (pin "1") (pinfunction "1_1") (pintype "passive"))
      (node (ref "C96") (pin "1") (pinfunction "1_1") (pintype "passive"))
      (node (ref "C97") (pin "1") (pinfunction "1_1") (pintype "passive"))
      (node (ref "C98") (pin "1") (pinfunction "1_1") (pintype "passive"))
      (node (ref "C99") (pin "1") (pinfunction "1_1") (pintype "passive"))
      (node (ref "P1") (pin "2") (pinfunction "GND_2") (pintype "passive"))
      (node (ref "U1") (pin "A1") (pinfunction "GND_A1") (pintype "power_in"))
      (node (ref "U1") (pin "A16") (pinfunction "GND_A16") (pintype "power_in"))
      (node (ref "U1") (pin "B11") (pinfunction "GND_B11") (pintype "power_in"))
      (node (ref "U1") (pin "B7") (pinfunction "GND_B7") (pintype "power_in"))
      (node (ref "U1") (pin "D13") (pinfunction "GND_D13") (pintype "power_in"))
      (node (ref "U1") (pin "D4") (pinfunction "GND_D4") (pintype "power_in"))
      (node (ref "U1") (pin "E9") (pinfunction "GND_E9") (pintype "power_in"))
      (node (ref "U1") (pin "G15") (pinfunction "GND_G15") (pintype "power_in"))
      (node (ref "U1") (pin "G2") (pinfunction "GND_G2") (pintype "power_in"))
      (node (ref "U1") (pin "G8") (pinfunction "GND_G8") (pintype "power_in"))
      (node (ref "U1") (pin "H12") (pinfunction "GND_H12") (pintype "power_in"))
      (node (ref "U1") (pin "H7") (pinfunction "GND_H7") (pintype "power_in"))
      (node (ref "U1") (pin "H9") (pinfunction "GND_H9") (pintype "power_in"))
      (node (ref "U1") (pin "J5") (pinfunction "GND_J5") (pintype "power_in"))
      (node (ref "U1") (pin "J8") (pinfunction "GND_J8") (pintype "power_in"))
      (node (ref "U1") (pin "K7") (pinfunction "GND_K7") (pintype "power_in"))
      (node (ref "U1") (pin "K9") (pinfunction "GND_K9") (pintype "power_in"))
      (node (ref "U1") (pin "L15") (pinfunction "GND_L15") (pintype "power_in"))
      (node (ref "U1") (pin "L2") (pinfunction "GND_L2") (pintype "power_in"))
      (node (ref "U1") (pin "M8") (pinfunction "GND_M8") (pintype "power_in"))
      (node (ref "U1") (pin "N13") (pinfunction "GND_N13") (pintype "power_in"))
      (node (ref "U1") (pin "P3") (pinfunction "GND_P3") (pintype "power_in"))
      (node (ref "U1") (pin "R10") (pinfunction "GND_R10") (pintype "power_in"))
      (node (ref "U1") (pin "R6") (pinfunction "GND_R6") (pintype "power_in"))
      (node (ref "U1") (pin "T1") (pinfunction "GND_T1") (pintype "power_in"))
      (node (ref "U1") (pin "T16") (pinfunction "GND_T16") (pintype "power_in"))
    )
    (net (code "110") (name "unconnected-(U1A-IO_L5N_0-PadE6)") (class "Default")
      (node (ref "U1") (pin "E6") (pinfunction "IO_L5N_0_E6") (pintype "bidirectional"))
    )
    (net (code "111") (name "unconnected-(U1A-IO_L5P_0-PadF7)") (class "Default")
      (node (ref "U1") (pin "F7") (pinfunction "IO_L5P_0_F7") (pintype "bidirectional"))
    )
    (net (code "112") (name "unconnected-(U1A-IO_L63N_SCP6_0-PadA13)") (class "Default")
      (node (ref "U1") (pin "A13") (pinfunction "IO_L63N_SCP6_0_A13") (pintype "bidirectional"))
    )
    (net (code "113") (name "unconnected-(U1A-IO_L63P_SCP7_0-PadC13)") (class "Default")
      (node (ref "U1") (pin "C13") (pinfunction "IO_L63P_SCP7_0_C13") (pintype "bidirectional"))
    )
    (net (code "114") (name "unconnected-(U1A-IO_L64N_SCP4_0-PadE11)") (class "Default")
      (node (ref "U1") (pin "E11") (pinfunction "IO_L64N_SCP4_0_E11") (pintype "bidirectional"))
    )
    (net (code "115") (name "unconnected-(U1A-IO_L64P_SCP5_0-PadF10)") (class "Default")
      (node (ref "U1") (pin "F10") (pinfunction "IO_L64P_SCP5_0_F10") (pintype "bidirectional"))
    )
    (net (code "116") (name "unconnected-(U1A-IO_L65N_SCP2_0-PadA14)") (class "Default")
      (node (ref "U1") (pin "A14") (pinfunction "IO_L65N_SCP2_0_A14") (pintype "bidirectional"))
    )
    (net (code "117") (name "unconnected-(U1A-IO_L65P_SCP3_0-PadB14)") (class "Default")
      (node (ref "U1") (pin "B14") (pinfunction "IO_L65P_SCP3_0_B14") (pintype "bidirectional"))
    )
    (net (code "118") (name "unconnected-(U1A-IO_L66N_SCP0_0-PadD12)") (class "Default")
      (node (ref "U1") (pin "D12") (pinfunction "IO_L66N_SCP0_0_D12") (pintype "bidirectional"))
    )
    (net (code "119") (name "unconnected-(U1A-IO_L66P_SCP1_0-PadD11)") (class "Default")
      (node (ref "U1") (pin "D11") (pinfunction "IO_L66P_SCP1_0_D11") (pintype "bidirectional"))
    )
    (net (code "120") (name "unconnected-(U1B-IO_L1N_A24_VREF_1-PadE12)") (class "Default")
      (node (ref "U1") (pin "E12") (pinfunction "IO_L1N_A24_VREF_1_E12") (pintype "bidirectional"))
    )
    (net (code "121") (name "unconnected-(U1B-IO_L1P_A25_1-PadE13)") (class "Default")
      (node (ref "U1") (pin "E13") (pinfunction "IO_L1P_A25_1_E13") (pintype "bidirectional"))
    )
    (net (code "122") (name "unconnected-(U1B-IO_L29N_A22_M1A14_1-PadB16)") (class "Default")
      (node (ref "U1") (pin "B16") (pinfunction "IO_L29N_A22_M1A14_1_B16") (pintype "bidirectional"))
    )
    (net (code "123") (name "unconnected-(U1B-IO_L29P_A23_M1A13_1-PadB15)") (class "Default")
      (node (ref "U1") (pin "B15") (pinfunction "IO_L29P_A23_M1A13_1_B15") (pintype "bidirectional"))
    )
    (net (code "124") (name "unconnected-(U1B-IO_L30N_A20_M1A11_1-PadG11)") (class "Default")
      (node (ref "U1") (pin "G11") (pinfunction "IO_L30N_A20_M1A11_1_G11") (pintype "bidirectional"))
    )
    (net (code "125") (name "unconnected-(U1B-IO_L30P_A21_M1RESET_1-PadF12)") (class "Default")
      (node (ref "U1") (pin "F12") (pinfunction "IO_L30P_A21_M1RESET_1_F12") (pintype "bidirectional"))
    )
    (net (code "126") (name "unconnected-(U1B-IO_L31N_A18_M1A12_1-PadD16)") (class "Default")
      (node (ref "U1") (pin "D16") (pinfunction "IO_L31N_A18_M1A12_1_D16") (pintype "bidirectional"))
    )
    (net (code "127") (name "unconnected-(U1B-IO_L31P_A19_M1CKE_1-PadD14)") (class "Default")
      (node (ref "U1") (pin "D14") (pinfunction "IO_L31P_A19_M1CKE_1_D14") (pintype "bidirectional"))
    )
    (net (code "128") (name "unconnected-(U1B-IO_L32N_A16_M1A9_1-PadF14)") (class "Default")
      (node (ref "U1") (pin "F14") (pinfunction "IO_L32N_A16_M1A9_1_F14") (pintype "bidirectional"))
    )
    (net (code "129") (name "unconnected-(U1B-IO_L32P_A17_M1A8_1-PadF13)") (class "Default")
      (node (ref "U1") (pin "F13") (pinfunction "IO_L32P_A17_M1A8_1_F13") (pintype "bidirectional"))
    )
    (net (code "130") (name "unconnected-(U1B-IO_L33N_A14_M1A4_1-PadC16)") (class "Default")
      (node (ref "U1") (pin "C16") (pinfunction "IO_L33N_A14_M1A4_1_C16") (pintype "bidirectional"))
    )
    (net (code "131") (name "unconnected-(U1B-IO_L33P_A15_M1A10_1-PadC15)") (class "Default")
      (node (ref "U1") (pin "C15") (pinfunction "IO_L33P_A15_M1A10_1_C15") (pintype "bidirectional"))
    )
    (net (code "132") (name "unconnected-(U1B-IO_L36P_A9_M1BA0_1-PadG14)") (class "Default")
      (node (ref "U1") (pin "G14") (pinfunction "IO_L36P_A9_M1BA0_1_G14") (pintype "bidirectional"))
    )
    (net (code "133") (name "unconnected-(U1B-IO_L38N_A4_M1CLKN_1-PadH11)") (class "Default")
      (node (ref "U1") (pin "H11") (pinfunction "IO_L38N_A4_M1CLKN_1_H11") (pintype "bidirectional"))
    )
    (net (code "134") (name "unconnected-(U1B-IO_L38P_A5_M1CLK_1-PadG12)") (class "Default")
      (node (ref "U1") (pin "G12") (pinfunction "IO_L38P_A5_M1CLK_1_G12") (pintype "bidirectional"))
    )
    (net (code "135") (name "unconnected-(U1B-IO_L39P_M1A3_1-PadH13)") (class "Default")
      (node (ref "U1") (pin "H13") (pinfunction "IO_L39P_M1A3_1_H13") (pintype "bidirectional"))
    )
    (net (code "136") (name "unconnected-(U1B-IO_L40N_GCLK10_M1A6_1-PadJ12)") (class "Default")
      (node (ref "U1") (pin "J12") (pinfunction "IO_L40N_GCLK10_M1A6_1_J12") (pintype "bidirectional"))
    )
    (net (code "137") (name "unconnected-(U1B-IO_L40P_GCLK11_M1A5_1-PadJ11)") (class "Default")
      (node (ref "U1") (pin "J11") (pinfunction "IO_L40P_GCLK11_M1A5_1_J11") (pintype "bidirectional"))
    )
    (net (code "138") (name "unconnected-(U1B-IO_L41P_GCLK9_IRDY1_M1RASN_1-PadJ13)") (class "Default")
      (node (ref "U1") (pin "J13") (pinfunction "IO_L41P_GCLK9_IRDY1_M1RASN_1_J13") (pintype "bidirectional"))
    )
    (net (code "139") (name "unconnected-(U1B-IO_L42N_GCLK6_TRDY1_M1LDM_1-PadK11)") (class "Default")
      (node (ref "U1") (pin "K11") (pinfunction "IO_L42N_GCLK6_TRDY1_M1LDM_1_K11") (pintype "bidirectional"))
    )
    (net (code "140") (name "unconnected-(U1B-IO_L42P_GCLK7_M1UDM_1-PadK12)") (class "Default")
      (node (ref "U1") (pin "K12") (pinfunction "IO_L42P_GCLK7_M1UDM_1_K12") (pintype "bidirectional"))
    )
    (net (code "141") (name "unconnected-(U1B-IO_L44P_A3_M1DQ6_1-PadK15)") (class "Default")
      (node (ref "U1") (pin "K15") (pinfunction "IO_L44P_A3_M1DQ6_1_K15") (pintype "bidirectional"))
    )
    (net (code "142") (name "unconnected-(U1B-IO_L45P_A1_M1LDQS_1-PadN14)") (class "Default")
      (node (ref "U1") (pin "N14") (pinfunction "IO_L45P_A1_M1LDQS_1_N14") (pintype "bidirectional"))
    )
    (net (code "143") (name "unconnected-(U1B-IO_L46P_FCS_B_M1DQ2_1-PadM15)") (class "Default")
      (node (ref "U1") (pin "M15") (pinfunction "IO_L46P_FCS_B_M1DQ2_1_M15") (pintype "bidirectional"))
    )
    (net (code "144") (name "unconnected-(U1B-IO_L53N_VREF_1-PadL13)") (class "Default")
      (node (ref "U1") (pin "L13") (pinfunction "IO_L53N_VREF_1_L13") (pintype "bidirectional"))
    )
    (net (code "145") (name "unconnected-(U1B-IO_L53P_1-PadL12)") (class "Default")
      (node (ref "U1") (pin "L12") (pinfunction "IO_L53P_1_L12") (pintype "bidirectional"))
    )
    (net (code "146") (name "unconnected-(U1B-IO_L74N_DOUT_BUSY_1-PadM14)") (class "Default")
      (node (ref "U1") (pin "M14") (pinfunction "IO_L74N_DOUT_BUSY_1_M14") (pintype "bidirectional"))
    )
    (net (code "147") (name "unconnected-(U1B-IO_L74P_AWAKE_1-PadM13)") (class "Default")
      (node (ref "U1") (pin "M13") (pinfunction "IO_L74P_AWAKE_1_M13") (pintype "bidirectional"))
    )
    (net (code "148") (name "unconnected-(U1C-IO_L29N_GCLK2_2-PadN8)") (class "Default")
      (node (ref "U1") (pin "N8") (pinfunction "IO_L29N_GCLK2_2_N8") (pintype "bidirectional"))
    )
    (net (code "149") (name "unconnected-(U1C-IO_L29P_GCLK3_2-PadM9)") (class "Default")
      (node (ref "U1") (pin "M9") (pinfunction "IO_L29P_GCLK3_2_M9") (pintype "bidirectional"))
    )
    (net (code "150") (name "unconnected-(U1C-IO_L62N_D6_2-PadL7)") (class "Default")
      (node (ref "U1") (pin "L7") (pinfunction "IO_L62N_D6_2_L7") (pintype "bidirectional"))
    )
    (net (code "151") (name "unconnected-(U1C-IO_L62P_D5_2-PadL8)") (class "Default")
      (node (ref "U1") (pin "L8") (pinfunction "IO_L62P_D5_2_L8") (pintype "bidirectional"))
    )
    (net (code "152") (name "unconnected-(U1D-IO_L1N_VREF_3-PadM3)") (class "Default")
      (node (ref "U1") (pin "M3") (pinfunction "IO_L1N_VREF_3_M3") (pintype "bidirectional"))
    )
    (net (code "153") (name "unconnected-(U1D-IO_L1P_3-PadM4)") (class "Default")
      (node (ref "U1") (pin "M4") (pinfunction "IO_L1P_3_M4") (pintype "bidirectional"))
    )
    (net (code "154") (name "unconnected-(U1D-IO_L2N_3-PadN4)") (class "Default")
      (node (ref "U1") (pin "N4") (pinfunction "IO_L2N_3_N4") (pintype "bidirectional"))
    )
    (net (code "155") (name "unconnected-(U1D-IO_L2P_3-PadM5)") (class "Default")
      (node (ref "U1") (pin "M5") (pinfunction "IO_L2P_3_M5") (pintype "bidirectional"))
    )
    (net (code "156") (name "unconnected-(U1D-IO_L32P_M3DQ14_3-PadR2)") (class "Default")
      (node (ref "U1") (pin "R2") (pinfunction "IO_L32P_M3DQ14_3_R2") (pintype "bidirectional"))
    )
    (net (code "157") (name "unconnected-(U1D-IO_L33P_M3DQ12_3-PadP2)") (class "Default")
      (node (ref "U1") (pin "P2") (pinfunction "IO_L33P_M3DQ12_3_P2") (pintype "bidirectional"))
    )
    (net (code "158") (name "unconnected-(U1D-IO_L34P_M3UDQS_3-PadN3)") (class "Default")
      (node (ref "U1") (pin "N3") (pinfunction "IO_L34P_M3UDQS_3_N3") (pintype "bidirectional"))
    )
    (net (code "159") (name "unconnected-(U1D-IO_L35P_M3DQ10_3-PadM2)") (class "Default")
      (node (ref "U1") (pin "M2") (pinfunction "IO_L35P_M3DQ10_3_M2") (pintype "bidirectional"))
    )
    (net (code "160") (name "unconnected-(U1D-IO_L36P_M3DQ8_3-PadL3)") (class "Default")
      (node (ref "U1") (pin "L3") (pinfunction "IO_L36P_M3DQ8_3_L3") (pintype "bidirectional"))
    )
    (net (code "161") (name "unconnected-(U1D-IO_L37P_M3DQ0_3-PadK2)") (class "Default")
      (node (ref "U1") (pin "K2") (pinfunction "IO_L37P_M3DQ0_3_K2") (pintype "bidirectional"))
    )
    (net (code "162") (name "unconnected-(U1D-IO_L38P_M3DQ2_3-PadJ3)") (class "Default")
      (node (ref "U1") (pin "J3") (pinfunction "IO_L38P_M3DQ2_3_J3") (pintype "bidirectional"))
    )
    (net (code "163") (name "unconnected-(U1D-IO_L39P_M3LDQS_3-PadH2)") (class "Default")
      (node (ref "U1") (pin "H2") (pinfunction "IO_L39P_M3LDQS_3_H2") (pintype "bidirectional"))
    )
    (net (code "164") (name "unconnected-(U1D-IO_L40P_M3DQ6_3-PadG3)") (class "Default")
      (node (ref "U1") (pin "G3") (pinfunction "IO_L40P_M3DQ6_3_G3") (pintype "bidirectional"))
    )
    (net (code "165") (name "unconnected-(U1D-IO_L41P_GCLK27_M3DQ4_3-PadF2)") (class "Default")
      (node (ref "U1") (pin "F2") (pinfunction "IO_L41P_GCLK27_M3DQ4_3_F2") (pintype "bidirectional"))
    )
    (net (code "166") (name "unconnected-(U1D-IO_L42N_GCLK24_M3LDM_3-PadJ4)") (class "Default")
      (node (ref "U1") (pin "J4") (pinfunction "IO_L42N_GCLK24_M3LDM_3_J4") (pintype "bidirectional"))
    )
    (net (code "167") (name "unconnected-(U1D-IO_L42P_GCLK25_TRDY2_M3UDM_3-PadK3)") (class "Default")
      (node (ref "U1") (pin "K3") (pinfunction "IO_L42P_GCLK25_TRDY2_M3UDM_3_K3") (pintype "bidirectional"))
    )
    (net (code "168") (name "unconnected-(U1D-IO_L43N_GCLK22_IRDY2_M3CASN_3-PadH5)") (class "Default")
      (node (ref "U1") (pin "H5") (pinfunction "IO_L43N_GCLK22_IRDY2_M3CASN_3_H5") (pintype "bidirectional"))
    )
    (net (code "169") (name "unconnected-(U1D-IO_L43P_GCLK23_M3RASN_3-PadJ6)") (class "Default")
      (node (ref "U1") (pin "J6") (pinfunction "IO_L43P_GCLK23_M3RASN_3_J6") (pintype "bidirectional"))
    )
    (net (code "170") (name "unconnected-(U1D-IO_L44N_GCLK20_M3A6_3-PadH3)") (class "Default")
      (node (ref "U1") (pin "H3") (pinfunction "IO_L44N_GCLK20_M3A6_3_H3") (pintype "bidirectional"))
    )
    (net (code "171") (name "unconnected-(U1D-IO_L44P_GCLK21_M3A5_3-PadH4)") (class "Default")
      (node (ref "U1") (pin "H4") (pinfunction "IO_L44P_GCLK21_M3A5_3_H4") (pintype "bidirectional"))
    )
    (net (code "172") (name "unconnected-(U1D-IO_L45N_M3ODT_3-PadL5)") (class "Default")
      (node (ref "U1") (pin "L5") (pinfunction "IO_L45N_M3ODT_3_L5") (pintype "bidirectional"))
    )
    (net (code "173") (name "unconnected-(U1D-IO_L45P_M3A3_3-PadL4)") (class "Default")
      (node (ref "U1") (pin "L4") (pinfunction "IO_L45P_M3A3_3_L4") (pintype "bidirectional"))
    )
    (net (code "174") (name "unconnected-(U1D-IO_L46P_M3CLK_3-PadE2)") (class "Default")
      (node (ref "U1") (pin "E2") (pinfunction "IO_L46P_M3CLK_3_E2") (pintype "bidirectional"))
    )
    (net (code "175") (name "unconnected-(U1D-IO_L47N_M3A1_3-PadK6)") (class "Default")
      (node (ref "U1") (pin "K6") (pinfunction "IO_L47N_M3A1_3_K6") (pintype "bidirectional"))
    )
    (net (code "176") (name "unconnected-(U1D-IO_L47P_M3A0_3-PadK5)") (class "Default")
      (node (ref "U1") (pin "K5") (pinfunction "IO_L47P_M3A0_3_K5") (pintype "bidirectional"))
    )
    (net (code "177") (name "unconnected-(U1D-IO_L48N_M3BA1_3-PadC2)") (class "Default")
      (node (ref "U1") (pin "C2") (pinfunction "IO_L48N_M3BA1_3_C2") (pintype "bidirectional"))
    )
    (net (code "178") (name "unconnected-(U1D-IO_L48P_M3BA0_3-PadC3)") (class "Default")
      (node (ref "U1") (pin "C3") (pinfunction "IO_L48P_M3BA0_3_C3") (pintype "bidirectional"))
    )
    (net (code "179") (name "unconnected-(U1D-IO_L49P_M3A7_3-PadD3)") (class "Default")
      (node (ref "U1") (pin "D3") (pinfunction "IO_L49P_M3A7_3_D3") (pintype "bidirectional"))
    )
    (net (code "180") (name "unconnected-(U1D-IO_L50N_M3BA2_3-PadB1)") (class "Default")
      (node (ref "U1") (pin "B1") (pinfunction "IO_L50N_M3BA2_3_B1") (pintype "bidirectional"))
    )
    (net (code "181") (name "unconnected-(U1D-IO_L50P_M3WE_3-PadC1)") (class "Default")
      (node (ref "U1") (pin "C1") (pinfunction "IO_L50P_M3WE_3_C1") (pintype "bidirectional"))
    )
    (net (code "182") (name "unconnected-(U1D-IO_L51N_M3A4_3-PadG5)") (class "Default")
      (node (ref "U1") (pin "G5") (pinfunction "IO_L51N_M3A4_3_G5") (pintype "bidirectional"))
    )
    (net (code "183") (name "unconnected-(U1D-IO_L51P_M3A10_3-PadG6)") (class "Default")
      (node (ref "U1") (pin "G6") (pinfunction "IO_L51P_M3A10_3_G6") (pintype "bidirectional"))
    )
    (net (code "184") (name "unconnected-(U1D-IO_L52N_M3A9_3-PadA2)") (class "Default")
      (node (ref "U1") (pin "A2") (pinfunction "IO_L52N_M3A9_3_A2") (pintype "bidirectional"))
    )
    (net (code "185") (name "unconnected-(U1D-IO_L52P_M3A8_3-PadB2)") (class "Default")
      (node (ref "U1") (pin "B2") (pinfunction "IO_L52P_M3A8_3_B2") (pintype "bidirectional"))
    )
    (net (code "186") (name "unconnected-(U1D-IO_L53N_M3A12_3-PadF3)") (class "Default")
      (node (ref "U1") (pin "F3") (pinfunction "IO_L53N_M3A12_3_F3") (pintype "bidirectional"))
    )
    (net (code "187") (name "unconnected-(U1D-IO_L53P_M3CKE_3-PadF4)") (class "Default")
      (node (ref "U1") (pin "F4") (pinfunction "IO_L53P_M3CKE_3_F4") (pintype "bidirectional"))
    )
    (net (code "188") (name "unconnected-(U1D-IO_L54N_M3A11_3-PadE3)") (class "Default")
      (node (ref "U1") (pin "E3") (pinfunction "IO_L54N_M3A11_3_E3") (pintype "bidirectional"))
    )
    (net (code "189") (name "unconnected-(U1D-IO_L54P_M3RESET_3-PadE4)") (class "Default")
      (node (ref "U1") (pin "E4") (pinfunction "IO_L54P_M3RESET_3_E4") (pintype "bidirectional"))
    )
    (net (code "190") (name "unconnected-(U1D-IO_L55N_M3A14_3-PadF5)") (class "Default")
      (node (ref "U1") (pin "F5") (pinfunction "IO_L55N_M3A14_3_F5") (pintype "bidirectional"))
    )
    (net (code "191") (name "unconnected-(U1D-IO_L55P_M3A13_3-PadF6)") (class "Default")
      (node (ref "U1") (pin "F6") (pinfunction "IO_L55P_M3A13_3_F6") (pintype "bidirectional"))
    )
    (net (code "192") (name "unconnected-(U1D-IO_L83N_VREF_3-PadA3)") (class "Default")
      (node (ref "U1") (pin "A3") (pinfunction "IO_L83N_VREF_3_A3") (pintype "bidirectional"))
    )
    (net (code "193") (name "unconnected-(U1D-IO_L83P_3-PadB3)") (class "Default")
      (node (ref "U1") (pin "B3") (pinfunction "IO_L83P_3_B3") (pintype "bidirectional"))
    )
    (net (code "194") (name "unconnected-(U1E-CMPCS_B_2-PadL11)") (class "Default")
      (node (ref "U1") (pin "L11") (pinfunction "CMPCS_B_2_L11") (pintype "input"))
    )
    (net (code "195") (name "unconnected-(U1E-DONE_2-PadP13)") (class "Default")
      (node (ref "U1") (pin "P13") (pinfunction "DONE_2_P13") (pintype "bidirectional"))
    )
    (net (code "196") (name "unconnected-(U1E-PROGRAM_B_2-PadT2)") (class "Default")
      (node (ref "U1") (pin "T2") (pinfunction "PROGRAM_B_2_T2") (pintype "input"))
    )
    (net (code "197") (name "unconnected-(U1E-SUSPEND-PadP14)") (class "Default")
      (node (ref "U1") (pin "P14") (pinfunction "SUSPEND_P14") (pintype "input"))
    )
  )
)
